# Luxeon_Turn.net
KiCad netlist of a schematic drawn in EAGLE
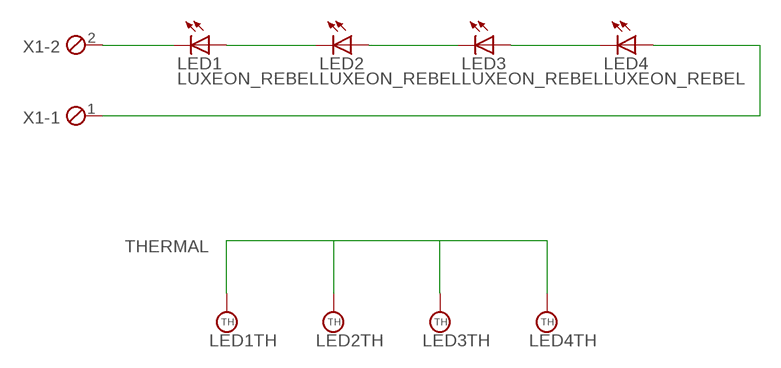
[diagram p0: schematic, sheet 1]

(export (version "E")
  (design (tool "Eeschema 10.0.6"))
  (components
    (comp (ref "LED1")
      (value "LUXEON_REBEL")
      (footprint "eagle-import:LUXEON_REBEL")
      (libsource (lib "eagle-import") (part "LUXEON_REBEL"))
    )
    (comp (ref "LED2")
      (value "LUXEON_REBEL")
      (footprint "eagle-import:LUXEON_REBEL")
      (libsource (lib "eagle-import") (part "LUXEON_REBEL"))
    )
    (comp (ref "LED3")
      (value "LUXEON_REBEL")
      (footprint "eagle-import:LUXEON_REBEL")
      (libsource (lib "eagle-import") (part "LUXEON_REBEL"))
    )
    (comp (ref "LED4")
      (value "LUXEON_REBEL")
      (footprint "eagle-import:LUXEON_REBEL")
      (libsource (lib "eagle-import") (part "LUXEON_REBEL"))
    )
    (comp (ref "X1")
      (value "MPT2")
      (footprint "eagle-import:2POL254")
      (libsource (lib "eagle-import") (part "MPT2"))
    )
  )
  (nets
    (net (code "1") (name "/THERMAL") (class "Default")
      (node (ref "LED1") (pin "TH") (pinfunction "TH_TH") (pintype "passive"))
      (node (ref "LED1") (pin "TH@1") (pinfunction "TH_TH@1") (pintype "passive"))
      (node (ref "LED1") (pin "TH@2") (pinfunction "TH_TH@2") (pintype "passive"))
      (node (ref "LED1") (pin "TH@3") (pinfunction "TH_TH@3") (pintype "passive"))
      (node (ref "LED1") (pin "TH@4") (pinfunction "TH_TH@4") (pintype "passive"))
      (node (ref "LED2") (pin "TH") (pinfunction "TH_TH") (pintype "passive"))
      (node (ref "LED2") (pin "TH@1") (pinfunction "TH_TH@1") (pintype "passive"))
      (node (ref "LED2") (pin "TH@2") (pinfunction "TH_TH@2") (pintype "passive"))
      (node (ref "LED2") (pin "TH@3") (pinfunction "TH_TH@3") (pintype "passive"))
      (node (ref "LED2") (pin "TH@4") (pinfunction "TH_TH@4") (pintype "passive"))
      (node (ref "LED3") (pin "TH") (pinfunction "TH_TH") (pintype "passive"))
      (node (ref "LED3") (pin "TH@1") (pinfunction "TH_TH@1") (pintype "passive"))
      (node (ref "LED3") (pin "TH@2") (pinfunction "TH_TH@2") (pintype "passive"))
      (node (ref "LED3") (pin "TH@3") (pinfunction "TH_TH@3") (pintype "passive"))
      (node (ref "LED3") (pin "TH@4") (pinfunction "TH_TH@4") (pintype "passive"))
      (node (ref "LED4") (pin "TH") (pinfunction "TH_TH") (pintype "passive"))
      (node (ref "LED4") (pin "TH@1") (pinfunction "TH_TH@1") (pintype "passive"))
      (node (ref "LED4") (pin "TH@2") (pinfunction "TH_TH@2") (pintype "passive"))
      (node (ref "LED4") (pin "TH@3") (pinfunction "TH_TH@3") (pintype "passive"))
      (node (ref "LED4") (pin "TH@4") (pinfunction "TH_TH@4") (pintype "passive"))
    )
    (net (code "2") (name "Net-(LED1-PadA)") (class "Default")
      (node (ref "LED1") (pin "A") (pinfunction "A_A") (pintype "passive"))
      (node (ref "LED1") (pin "A@1") (pinfunction "A_A@1") (pintype "passive"))
      (node (ref "LED2") (pin "C") (pinfunction "C_C") (pintype "passive"))
      (node (ref "LED2") (pin "C@1") (pinfunction "C_C@1") (pintype "passive"))
    )
    (net (code "3") (name "Net-(LED2-PadA)") (class "Default")
      (node (ref "LED2") (pin "A") (pinfunction "A_A") (pintype "passive"))
      (node (ref "LED2") (pin "A@1") (pinfunction "A_A@1") (pintype "passive"))
      (node (ref "LED3") (pin "C") (pinfunction "C_C") (pintype "passive"))
      (node (ref "LED3") (pin "C@1") (pinfunction "C_C@1") (pintype "passive"))
    )
    (net (code "4") (name "Net-(LED3-PadA)") (class "Default")
      (node (ref "LED3") (pin "A") (pinfunction "A_A") (pintype "passive"))
      (node (ref "LED3") (pin "A@1") (pinfunction "A_A@1") (pintype "passive"))
      (node (ref "LED4") (pin "C") (pinfunction "C_C") (pintype "passive"))
      (node (ref "LED4") (pin "C@1") (pinfunction "C_C@1") (pintype "passive"))
    )
    (net (code "5") (name "Net-(LED4-PadA)") (class "Default")
      (node (ref "LED4") (pin "A") (pinfunction "A_A") (pintype "passive"))
      (node (ref "LED4") (pin "A@1") (pinfunction "A_A@1") (pintype "passive"))
      (node (ref "X1") (pin "1") (pinfunction "1_1") (pintype "passive"))
    )
    (net (code "6") (name "Net-(X1B-1)") (class "Default")
      (node (ref "LED1") (pin "C") (pinfunction "C_C") (pintype "passive"))
      (node (ref "LED1") (pin "C@1") (pinfunction "C_C@1") (pintype "passive"))
      (node (ref "X1") (pin "2") (pinfunction "1_2") (pintype "passive"))
    )
  )
)
